# AMU-S21-V00-CURRENT5kWDetection.net
KiCad netlist of a schematic drawn in Altium Designer
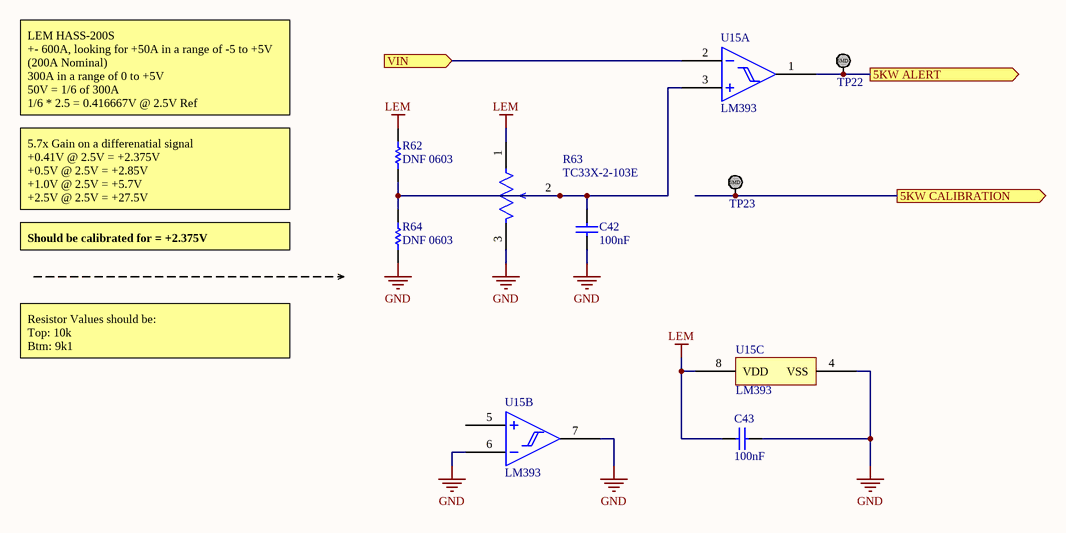
[diagram p0: AMU-S21-V00-CURRENT5kWDetection.SchDoc]

(export (version "E")
  (design (tool "Eeschema 10.0.6"))
  (components
    (comp (ref "C42")
      (value "100nF")
      (footprint "Cap_Ceramic_0603")
      (description "Capacitor, Ceramic, SMD, 100nF, 50V, 5%, X7R, 0603")
      (libsource (lib "StandardCapacitors") (part "100nF 50V 5% X7R 0603"))
    )
    (comp (ref "C43")
      (value "100nF")
      (footprint "Cap_Ceramic_0603")
      (description "Capacitor, Ceramic, SMD, 100nF, 50V, 5%, X7R, 0603")
      (libsource (lib "StandardCapacitors") (part "100nF 50V 5% X7R 0603"))
    )
    (comp (ref "R62")
      (value "DNF 0603")
      (footprint "Res_ThinFilm_0603")
      (description "Resistor, SMD, DNF, 0.1W, 0603")
      (libsource (lib "StandardResistors") (part "DNF 0603"))
    )
    (comp (ref "R63")
      (value "TC33X-2-103E")
      (footprint "TC33")
      (description "10 kOhms 0.1W, 1/10W J Lead Surface Mount Trimmer Potentiometer Cermet 1 Turn Top Adjustment")
      (libsource (lib "QUTMS_TrimmerLibrary") (part "TC33X-2-103E"))
    )
    (comp (ref "R64")
      (value "DNF 0603")
      (footprint "Res_ThinFilm_0603")
      (description "Resistor, SMD, DNF, 0.1W, 0603")
      (libsource (lib "StandardResistors") (part "DNF 0603"))
    )
    (comp (ref "TP22")
      (value "TestPoint_SMD")
      (footprint "TestPointSMD")
      (libsource (lib "StandardTest") (part "TestPoint_SMD"))
    )
    (comp (ref "TP23")
      (value "TestPoint_SMD")
      (footprint "TestPointSMD")
      (libsource (lib "StandardTest") (part "TestPoint_SMD"))
    )
    (comp (ref "U15")
      (value "LM393")
      (footprint "TSSOP-8")
      (description "General Purpose Comparitor 2 Circuit 8-SOIC")
      (libsource (lib "") (part "LM393_1"))
    )
  )
  (nets
    (net (code "1") (name "/5KW ALERT") (class "Default")
      (node (ref "TP22") (pin "1") (pinfunction "1_1") (pintype "passive"))
      (node (ref "U15") (pin "1") (pinfunction "OUT1_1") (pintype "passive"))
    )
    (net (code "2") (name "/5KW CALIBRATION") (class "Default")
      (node (ref "TP23") (pin "1") (pinfunction "1_1") (pintype "passive"))
    )
    (net (code "3") (name "/VIN") (class "Default")
      (node (ref "U15") (pin "2") (pinfunction "IN1-_2") (pintype "passive"))
    )
    (net (code "4") (name "GND") (class "Default")
      (node (ref "C42") (pin "1") (pinfunction "1_1") (pintype "passive"))
      (node (ref "C43") (pin "2") (pinfunction "2_2") (pintype "passive"))
      (node (ref "R63") (pin "3") (pinfunction "3_3") (pintype "passive"))
      (node (ref "R64") (pin "1") (pinfunction "1_1") (pintype "passive"))
      (node (ref "U15") (pin "4") (pinfunction "VSS_4") (pintype "passive"))
      (node (ref "U15") (pin "6") (pinfunction "IN2-_6") (pintype "passive"))
      (node (ref "U15") (pin "7") (pinfunction "OUT1_7") (pintype "passive"))
    )
    (net (code "5") (name "LEM") (class "Default")
      (node (ref "C43") (pin "1") (pinfunction "1_1") (pintype "passive"))
      (node (ref "R62") (pin "2") (pinfunction "2_2") (pintype "passive"))
      (node (ref "R63") (pin "1") (pinfunction "1_1") (pintype "passive"))
      (node (ref "U15") (pin "8") (pinfunction "VDD_8") (pintype "passive"))
    )
    (net (code "6") (name "Net-(U15A-IN1+)") (class "Default")
      (node (ref "C42") (pin "2") (pinfunction "2_2") (pintype "passive"))
      (node (ref "R62") (pin "1") (pinfunction "1_1") (pintype "passive"))
      (node (ref "R63") (pin "2") (pinfunction "2_2") (pintype "passive"))
      (node (ref "R64") (pin "2") (pinfunction "2_2") (pintype "passive"))
      (node (ref "U15") (pin "3") (pinfunction "IN1+_3") (pintype "passive"))
    )
    (net (code "7") (name "unconnected-(U15B-IN2+-Pad5)") (class "Default")
      (node (ref "U15") (pin "5") (pinfunction "IN2+_5") (pintype "passive"))
    )
  )
)
